# osi-proto.net
KiCad netlist of a schematic drawn in EAGLE
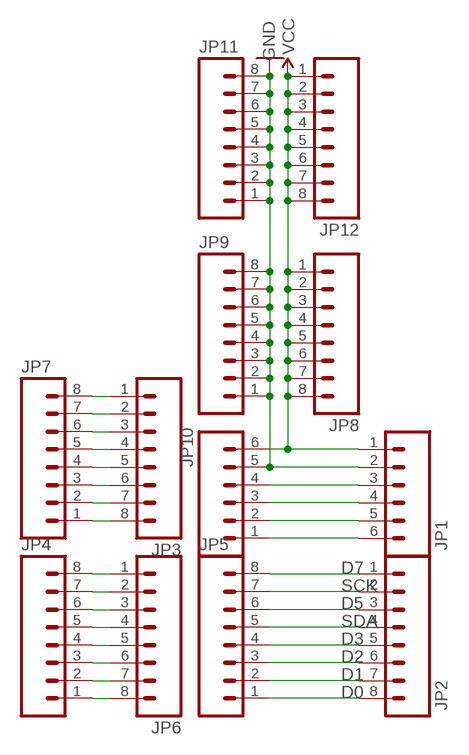
[diagram p0: schematic, sheet 1]

(export (version "E")
  (design (tool "Eeschema 10.0.6"))
  (components
    (comp (ref "JP1")
      (value "M06SIP")
      (footprint "eagle-import:1X06")
      (libsource (lib "eagle-import") (part "M06SIP"))
    )
    (comp (ref "JP2")
      (value "M081X08")
      (footprint "eagle-import:1X08")
      (libsource (lib "eagle-import") (part "M081X08"))
    )
    (comp (ref "JP3")
      (value "M081X08")
      (footprint "eagle-import:1X08")
      (libsource (lib "eagle-import") (part "M081X08"))
    )
    (comp (ref "JP4")
      (value "M081X08")
      (footprint "eagle-import:1X08")
      (libsource (lib "eagle-import") (part "M081X08"))
    )
    (comp (ref "JP5")
      (value "M081X08")
      (footprint "eagle-import:1X08")
      (libsource (lib "eagle-import") (part "M081X08"))
    )
    (comp (ref "JP6")
      (value "M081X08")
      (footprint "eagle-import:1X08")
      (libsource (lib "eagle-import") (part "M081X08"))
    )
    (comp (ref "JP7")
      (value "M081X08")
      (footprint "eagle-import:1X08")
      (libsource (lib "eagle-import") (part "M081X08"))
    )
    (comp (ref "JP8")
      (value "M081X08")
      (footprint "eagle-import:1X08")
      (libsource (lib "eagle-import") (part "M081X08"))
    )
    (comp (ref "JP9")
      (value "M081X08")
      (footprint "eagle-import:1X08")
      (libsource (lib "eagle-import") (part "M081X08"))
    )
    (comp (ref "JP10")
      (value "M06SIP")
      (footprint "eagle-import:1X06")
      (libsource (lib "eagle-import") (part "M06SIP"))
    )
    (comp (ref "JP11")
      (value "M081X08")
      (footprint "eagle-import:1X08")
      (libsource (lib "eagle-import") (part "M081X08"))
    )
    (comp (ref "JP12")
      (value "M081X08")
      (footprint "eagle-import:1X08")
      (libsource (lib "eagle-import") (part "M081X08"))
    )
  )
  (nets
    (net (code "1") (name "/D0") (class "Default")
      (node (ref "JP2") (pin "8") (pinfunction "8_8") (pintype "passive"))
      (node (ref "JP5") (pin "1") (pinfunction "1_1") (pintype "passive"))
    )
    (net (code "2") (name "/D1") (class "Default")
      (node (ref "JP2") (pin "7") (pinfunction "7_7") (pintype "passive"))
      (node (ref "JP5") (pin "2") (pinfunction "2_2") (pintype "passive"))
    )
    (net (code "3") (name "/D2") (class "Default")
      (node (ref "JP2") (pin "6") (pinfunction "6_6") (pintype "passive"))
      (node (ref "JP5") (pin "3") (pinfunction "3_3") (pintype "passive"))
    )
    (net (code "4") (name "/D3") (class "Default")
      (node (ref "JP2") (pin "5") (pinfunction "5_5") (pintype "passive"))
      (node (ref "JP5") (pin "4") (pinfunction "4_4") (pintype "passive"))
    )
    (net (code "5") (name "/D5") (class "Default")
      (node (ref "JP2") (pin "3") (pinfunction "3_3") (pintype "passive"))
      (node (ref "JP5") (pin "6") (pinfunction "6_6") (pintype "passive"))
    )
    (net (code "6") (name "/D7") (class "Default")
      (node (ref "JP2") (pin "1") (pinfunction "1_1") (pintype "passive"))
      (node (ref "JP5") (pin "8") (pinfunction "8_8") (pintype "passive"))
    )
    (net (code "7") (name "/SCK") (class "Default")
      (node (ref "JP2") (pin "2") (pinfunction "2_2") (pintype "passive"))
      (node (ref "JP5") (pin "7") (pinfunction "7_7") (pintype "passive"))
    )
    (net (code "8") (name "/SDA") (class "Default")
      (node (ref "JP2") (pin "4") (pinfunction "4_4") (pintype "passive"))
      (node (ref "JP5") (pin "5") (pinfunction "5_5") (pintype "passive"))
    )
    (net (code "9") (name "GND") (class "Default")
      (node (ref "JP1") (pin "2") (pinfunction "2_2") (pintype "passive"))
      (node (ref "JP10") (pin "5") (pinfunction "5_5") (pintype "passive"))
      (node (ref "JP11") (pin "1") (pinfunction "1_1") (pintype "passive"))
      (node (ref "JP11") (pin "2") (pinfunction "2_2") (pintype "passive"))
      (node (ref "JP11") (pin "3") (pinfunction "3_3") (pintype "passive"))
      (node (ref "JP11") (pin "4") (pinfunction "4_4") (pintype "passive"))
      (node (ref "JP11") (pin "5") (pinfunction "5_5") (pintype "passive"))
      (node (ref "JP11") (pin "6") (pinfunction "6_6") (pintype "passive"))
      (node (ref "JP11") (pin "7") (pinfunction "7_7") (pintype "passive"))
      (node (ref "JP11") (pin "8") (pinfunction "8_8") (pintype "passive"))
      (node (ref "JP9") (pin "1") (pinfunction "1_1") (pintype "passive"))
      (node (ref "JP9") (pin "2") (pinfunction "2_2") (pintype "passive"))
      (node (ref "JP9") (pin "3") (pinfunction "3_3") (pintype "passive"))
      (node (ref "JP9") (pin "4") (pinfunction "4_4") (pintype "passive"))
      (node (ref "JP9") (pin "5") (pinfunction "5_5") (pintype "passive"))
      (node (ref "JP9") (pin "6") (pinfunction "6_6") (pintype "passive"))
      (node (ref "JP9") (pin "7") (pinfunction "7_7") (pintype "passive"))
      (node (ref "JP9") (pin "8") (pinfunction "8_8") (pintype "passive"))
    )
    (net (code "10") (name "Net-(JP1-Pad3)") (class "Default")
      (node (ref "JP1") (pin "3") (pinfunction "3_3") (pintype "passive"))
      (node (ref "JP10") (pin "4") (pinfunction "4_4") (pintype "passive"))
    )
    (net (code "11") (name "Net-(JP1-Pad4)") (class "Default")
      (node (ref "JP1") (pin "4") (pinfunction "4_4") (pintype "passive"))
      (node (ref "JP10") (pin "3") (pinfunction "3_3") (pintype "passive"))
    )
    (net (code "12") (name "Net-(JP1-Pad5)") (class "Default")
      (node (ref "JP1") (pin "5") (pinfunction "5_5") (pintype "passive"))
      (node (ref "JP10") (pin "2") (pinfunction "2_2") (pintype "passive"))
    )
    (net (code "13") (name "Net-(JP1-Pad6)") (class "Default")
      (node (ref "JP1") (pin "6") (pinfunction "6_6") (pintype "passive"))
      (node (ref "JP10") (pin "1") (pinfunction "1_1") (pintype "passive"))
    )
    (net (code "14") (name "Net-(JP3-Pad1)") (class "Default")
      (node (ref "JP3") (pin "1") (pinfunction "1_1") (pintype "passive"))
      (node (ref "JP7") (pin "8") (pinfunction "8_8") (pintype "passive"))
    )
    (net (code "15") (name "Net-(JP3-Pad2)") (class "Default")
      (node (ref "JP3") (pin "2") (pinfunction "2_2") (pintype "passive"))
      (node (ref "JP7") (pin "7") (pinfunction "7_7") (pintype "passive"))
    )
    (net (code "16") (name "Net-(JP3-Pad3)") (class "Default")
      (node (ref "JP3") (pin "3") (pinfunction "3_3") (pintype "passive"))
      (node (ref "JP7") (pin "6") (pinfunction "6_6") (pintype "passive"))
    )
    (net (code "17") (name "Net-(JP3-Pad4)") (class "Default")
      (node (ref "JP3") (pin "4") (pinfunction "4_4") (pintype "passive"))
      (node (ref "JP7") (pin "5") (pinfunction "5_5") (pintype "passive"))
    )
    (net (code "18") (name "Net-(JP3-Pad5)") (class "Default")
      (node (ref "JP3") (pin "5") (pinfunction "5_5") (pintype "passive"))
      (node (ref "JP7") (pin "4") (pinfunction "4_4") (pintype "passive"))
    )
    (net (code "19") (name "Net-(JP3-Pad6)") (class "Default")
      (node (ref "JP3") (pin "6") (pinfunction "6_6") (pintype "passive"))
      (node (ref "JP7") (pin "3") (pinfunction "3_3") (pintype "passive"))
    )
    (net (code "20") (name "Net-(JP3-Pad7)") (class "Default")
      (node (ref "JP3") (pin "7") (pinfunction "7_7") (pintype "passive"))
      (node (ref "JP7") (pin "2") (pinfunction "2_2") (pintype "passive"))
    )
    (net (code "21") (name "Net-(JP3-Pad8)") (class "Default")
      (node (ref "JP3") (pin "8") (pinfunction "8_8") (pintype "passive"))
      (node (ref "JP7") (pin "1") (pinfunction "1_1") (pintype "passive"))
    )
    (net (code "22") (name "Net-(JP4-Pad1)") (class "Default")
      (node (ref "JP4") (pin "1") (pinfunction "1_1") (pintype "passive"))
      (node (ref "JP6") (pin "8") (pinfunction "8_8") (pintype "passive"))
    )
    (net (code "23") (name "Net-(JP4-Pad2)") (class "Default")
      (node (ref "JP4") (pin "2") (pinfunction "2_2") (pintype "passive"))
      (node (ref "JP6") (pin "7") (pinfunction "7_7") (pintype "passive"))
    )
    (net (code "24") (name "Net-(JP4-Pad3)") (class "Default")
      (node (ref "JP4") (pin "3") (pinfunction "3_3") (pintype "passive"))
      (node (ref "JP6") (pin "6") (pinfunction "6_6") (pintype "passive"))
    )
    (net (code "25") (name "Net-(JP4-Pad4)") (class "Default")
      (node (ref "JP4") (pin "4") (pinfunction "4_4") (pintype "passive"))
      (node (ref "JP6") (pin "5") (pinfunction "5_5") (pintype "passive"))
    )
    (net (code "26") (name "Net-(JP4-Pad5)") (class "Default")
      (node (ref "JP4") (pin "5") (pinfunction "5_5") (pintype "passive"))
      (node (ref "JP6") (pin "4") (pinfunction "4_4") (pintype "passive"))
    )
    (net (code "27") (name "Net-(JP4-Pad6)") (class "Default")
      (node (ref "JP4") (pin "6") (pinfunction "6_6") (pintype "passive"))
      (node (ref "JP6") (pin "3") (pinfunction "3_3") (pintype "passive"))
    )
    (net (code "28") (name "Net-(JP4-Pad7)") (class "Default")
      (node (ref "JP4") (pin "7") (pinfunction "7_7") (pintype "passive"))
      (node (ref "JP6") (pin "2") (pinfunction "2_2") (pintype "passive"))
    )
    (net (code "29") (name "Net-(JP4-Pad8)") (class "Default")
      (node (ref "JP4") (pin "8") (pinfunction "8_8") (pintype "passive"))
      (node (ref "JP6") (pin "1") (pinfunction "1_1") (pintype "passive"))
    )
    (net (code "30") (name "VCC") (class "Default")
      (node (ref "JP1") (pin "1") (pinfunction "1_1") (pintype "passive"))
      (node (ref "JP10") (pin "6") (pinfunction "6_6") (pintype "passive"))
      (node (ref "JP12") (pin "1") (pinfunction "1_1") (pintype "passive"))
      (node (ref "JP12") (pin "2") (pinfunction "2_2") (pintype "passive"))
      (node (ref "JP12") (pin "3") (pinfunction "3_3") (pintype "passive"))
      (node (ref "JP12") (pin "4") (pinfunction "4_4") (pintype "passive"))
      (node (ref "JP12") (pin "5") (pinfunction "5_5") (pintype "passive"))
      (node (ref "JP12") (pin "6") (pinfunction "6_6") (pintype "passive"))
      (node (ref "JP12") (pin "7") (pinfunction "7_7") (pintype "passive"))
      (node (ref "JP12") (pin "8") (pinfunction "8_8") (pintype "passive"))
      (node (ref "JP8") (pin "1") (pinfunction "1_1") (pintype "passive"))
      (node (ref "JP8") (pin "2") (pinfunction "2_2") (pintype "passive"))
      (node (ref "JP8") (pin "3") (pinfunction "3_3") (pintype "passive"))
      (node (ref "JP8") (pin "4") (pinfunction "4_4") (pintype "passive"))
      (node (ref "JP8") (pin "5") (pinfunction "5_5") (pintype "passive"))
      (node (ref "JP8") (pin "6") (pinfunction "6_6") (pintype "passive"))
      (node (ref "JP8") (pin "7") (pinfunction "7_7") (pintype "passive"))
      (node (ref "JP8") (pin "8") (pinfunction "8_8") (pintype "passive"))
    )
  )
)
